# Sheet.net
KiCad netlist of a schematic drawn in Altium Designer
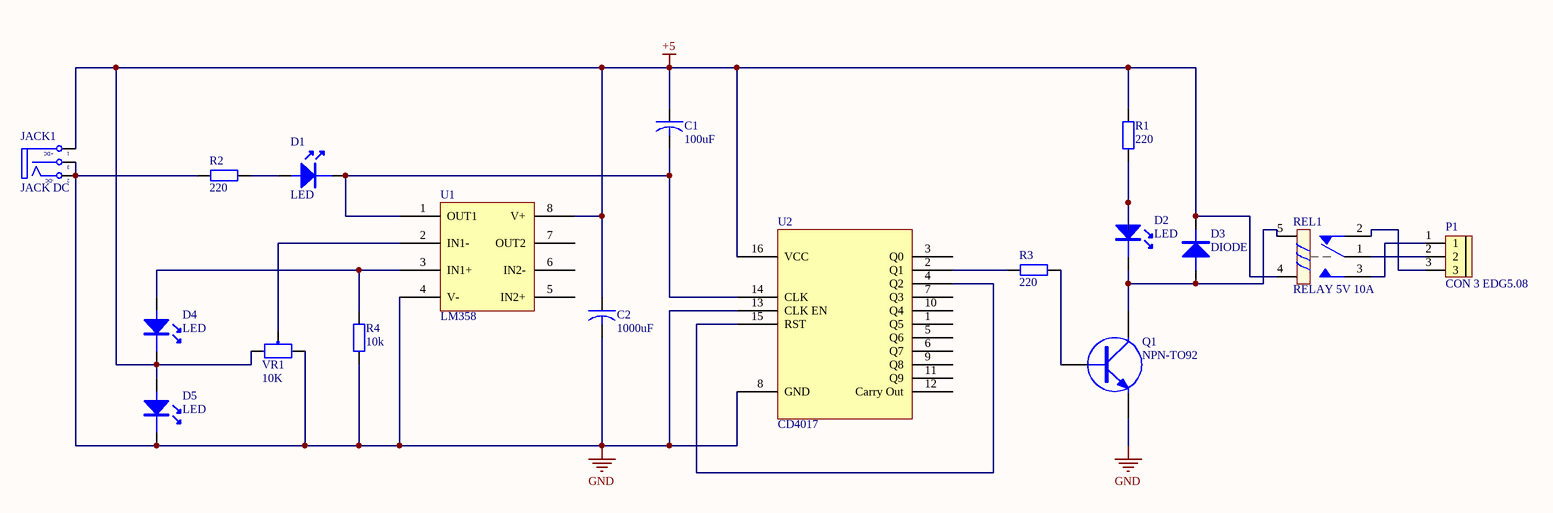
[diagram p0: Sheet.SchDoc]

(export (version "E")
  (design (tool "Eeschema 10.0.6"))
  (components
    (comp (ref "C1") (value "100uF") (footprint "TU HOA 8mm") (libsource (lib "bethu") (part "CAPACITOR")))
    (comp (ref "C2") (value "1000uF") (footprint "TU HOA 8mm") (libsource (lib "bethu") (part "CAPACITOR")))
    (comp (ref "D1") (value "LED") (footprint "LED5MM RED") (libsource (lib "bethu") (part "LED")))
    (comp (ref "D2") (value "LED") (footprint "LED5MM RED") (libsource (lib "bethu") (part "LED")))
    (comp (ref "D3") (value "DIODE") (footprint "DIODE 1A") (libsource (lib "bethu") (part "DIODE")))
    (comp (ref "D4") (value "LED") (footprint "LED5MM RED") (libsource (lib "bethu") (part "LED")))
    (comp (ref "D5") (value "LED") (footprint "LED5MM RED") (libsource (lib "bethu") (part "LED")))
    (comp (ref "JACK1") (value "JACK DC") (footprint "JACK DC") (libsource (lib "bethu") (part "JACK DC")))
    (comp (ref "P1")
      (value "CON 3 EDG5.08")
      (footprint "CON 3P 5.08MM")
      (description "Cắm")
      (libsource (lib "bethu") (part "CON 3 EDG5.08"))
    )
    (comp (ref "Q1") (value "NPN-TO92") (footprint "TO-92") (libsource (lib "bethu") (part "NPN-TO92")))
    (comp (ref "R1") (value "220") (footprint "RESISTOR") (libsource (lib "bethu") (part "RESISTOR")))
    (comp (ref "R2") (value "220") (footprint "RESISTOR") (libsource (lib "bethu") (part "RESISTOR")))
    (comp (ref "R3") (value "220") (footprint "RESISTOR") (libsource (lib "bethu") (part "RESISTOR")))
    (comp (ref "R4") (value "10k") (footprint "RESISTOR") (libsource (lib "bethu") (part "RESISTOR")))
    (comp (ref "REL1")
      (value "RELAY 5V 10A")
      (footprint "RELAY 5V-10A")
      (libsource (lib "bethu") (part "RELAY 5V 10A"))
    )
    (comp (ref "U1") (value "LM358") (footprint "DIP 8") (libsource (lib "bethu") (part "LM358")))
    (comp (ref "U2") (value "CD4017") (footprint "PDIP16") (libsource (lib "bethu") (part "CD4017")))
    (comp (ref "VR1") (value "10K") (footprint "RVAR") (libsource (lib "bethu") (part "VAR RES")))
  )
  (nets
    (net (code "1") (name "+5") (class "Default")
      (node (ref "C1") (pin "1") (pinfunction "1_1") (pintype "passive"))
      (node (ref "C2") (pin "1") (pinfunction "1_1") (pintype "passive"))
      (node (ref "D3") (pin "2") (pinfunction "2_2") (pintype "passive"))
      (node (ref "D4") (pin "2") (pinfunction "2_2") (pintype "passive"))
      (node (ref "D5") (pin "1") (pinfunction "1_1") (pintype "passive"))
      (node (ref "JACK1") (pin "1") (pinfunction "T_1") (pintype "passive"))
      (node (ref "R1") (pin "1") (pinfunction "1_1") (pintype "passive"))
      (node (ref "REL1") (pin "4") (pinfunction "4_4") (pintype "passive"))
      (node (ref "U1") (pin "8") (pinfunction "V+_8") (pintype "passive"))
      (node (ref "U2") (pin "16") (pinfunction "VCC_16") (pintype "passive"))
      (node (ref "VR1") (pin "1") (pinfunction "1_1") (pintype "passive"))
    )
    (net (code "2") (name "GND") (class "Default")
      (node (ref "C2") (pin "2") (pinfunction "2_2") (pintype "passive"))
      (node (ref "D5") (pin "2") (pinfunction "2_2") (pintype "passive"))
      (node (ref "JACK1") (pin "2") (pinfunction "TN_2") (pintype "passive"))
      (node (ref "JACK1") (pin "3") (pinfunction "S_3") (pintype "power_in"))
      (node (ref "Q1") (pin "1") (pinfunction "E_1") (pintype "passive"))
      (node (ref "R2") (pin "1") (pinfunction "1_1") (pintype "passive"))
      (node (ref "R4") (pin "1") (pinfunction "1_1") (pintype "passive"))
      (node (ref "U1") (pin "4") (pinfunction "V-_4") (pintype "passive"))
      (node (ref "U2") (pin "13") (pinfunction "CLK_EN_13") (pintype "passive"))
      (node (ref "U2") (pin "8") (pinfunction "GND_8") (pintype "passive"))
      (node (ref "VR1") (pin "3") (pinfunction "3_3") (pintype "passive"))
    )
    (net (code "3") (name "Net-(D1-Pad1)") (class "Default")
      (node (ref "D1") (pin "1") (pinfunction "1_1") (pintype "passive"))
      (node (ref "R2") (pin "2") (pinfunction "2_2") (pintype "passive"))
    )
    (net (code "4") (name "Net-(D2-Pad1)") (class "Default")
      (node (ref "D2") (pin "1") (pinfunction "1_1") (pintype "passive"))
      (node (ref "R1") (pin "2") (pinfunction "2_2") (pintype "passive"))
    )
    (net (code "5") (name "Net-(P1-Pad1)") (class "Default")
      (node (ref "P1") (pin "1") (pinfunction "1_1") (pintype "passive"))
      (node (ref "REL1") (pin "3") (pinfunction "3_3") (pintype "passive"))
    )
    (net (code "6") (name "Net-(P1-Pad2)") (class "Default")
      (node (ref "P1") (pin "2") (pinfunction "2_2") (pintype "passive"))
      (node (ref "REL1") (pin "1") (pinfunction "1_1") (pintype "passive"))
    )
    (net (code "7") (name "Net-(P1-Pad3)") (class "Default")
      (node (ref "P1") (pin "3") (pinfunction "3_3") (pintype "passive"))
      (node (ref "REL1") (pin "2") (pinfunction "2_2") (pintype "passive"))
    )
    (net (code "8") (name "Net-(Q1-B)") (class "Default")
      (node (ref "Q1") (pin "3") (pinfunction "B_3") (pintype "passive"))
      (node (ref "R3") (pin "2") (pinfunction "2_2") (pintype "passive"))
    )
    (net (code "9") (name "Net-(Q1-C)") (class "Default")
      (node (ref "D2") (pin "2") (pinfunction "2_2") (pintype "passive"))
      (node (ref "D3") (pin "1") (pinfunction "1_1") (pintype "passive"))
      (node (ref "Q1") (pin "2") (pinfunction "C_2") (pintype "passive"))
      (node (ref "REL1") (pin "5") (pinfunction "5_5") (pintype "passive"))
    )
    (net (code "10") (name "Net-(U1-IN1+)") (class "Default")
      (node (ref "D4") (pin "1") (pinfunction "1_1") (pintype "passive"))
      (node (ref "R4") (pin "2") (pinfunction "2_2") (pintype "passive"))
      (node (ref "U1") (pin "3") (pinfunction "IN1+_3") (pintype "passive"))
    )
    (net (code "11") (name "Net-(U1-IN1-)") (class "Default")
      (node (ref "U1") (pin "2") (pinfunction "IN1-_2") (pintype "passive"))
      (node (ref "VR1") (pin "2") (pinfunction "2_2") (pintype "passive"))
    )
    (net (code "12") (name "Net-(U1-OUT1)") (class "Default")
      (node (ref "C1") (pin "2") (pinfunction "2_2") (pintype "passive"))
      (node (ref "D1") (pin "2") (pinfunction "2_2") (pintype "passive"))
      (node (ref "U1") (pin "1") (pinfunction "OUT1_1") (pintype "passive"))
      (node (ref "U2") (pin "14") (pinfunction "CLK_14") (pintype "passive"))
    )
    (net (code "13") (name "Net-(U2-Q1)") (class "Default")
      (node (ref "R3") (pin "1") (pinfunction "1_1") (pintype "passive"))
      (node (ref "U2") (pin "2") (pinfunction "Q1_2") (pintype "passive"))
    )
    (net (code "14") (name "Net-(U2-Q2)") (class "Default")
      (node (ref "U2") (pin "15") (pinfunction "RST_15") (pintype "passive"))
      (node (ref "U2") (pin "4") (pinfunction "Q2_4") (pintype "passive"))
    )
    (net (code "15") (name "unconnected-(U1-IN2+-Pad5)") (class "Default")
      (node (ref "U1") (pin "5") (pinfunction "IN2+_5") (pintype "passive"))
    )
    (net (code "16") (name "unconnected-(U1-IN2--Pad6)") (class "Default")
      (node (ref "U1") (pin "6") (pinfunction "IN2-_6") (pintype "passive"))
    )
    (net (code "17") (name "unconnected-(U1-OUT2-Pad7)") (class "Default")
      (node (ref "U1") (pin "7") (pinfunction "OUT2_7") (pintype "passive"))
    )
    (net (code "18") (name "unconnected-(U2-Carry_Out-Pad12)") (class "Default")
      (node (ref "U2") (pin "12") (pinfunction "Carry_Out_12") (pintype "passive"))
    )
    (net (code "19") (name "unconnected-(U2-Q0-Pad3)") (class "Default")
      (node (ref "U2") (pin "3") (pinfunction "Q0_3") (pintype "passive"))
    )
    (net (code "20") (name "unconnected-(U2-Q3-Pad7)") (class "Default")
      (node (ref "U2") (pin "7") (pinfunction "Q3_7") (pintype "passive"))
    )
    (net (code "21") (name "unconnected-(U2-Q4-Pad10)") (class "Default")
      (node (ref "U2") (pin "10") (pinfunction "Q4_10") (pintype "passive"))
    )
    (net (code "22") (name "unconnected-(U2-Q5-Pad1)") (class "Default")
      (node (ref "U2") (pin "1") (pinfunction "Q5_1") (pintype "passive"))
    )
    (net (code "23") (name "unconnected-(U2-Q6-Pad5)") (class "Default")
      (node (ref "U2") (pin "5") (pinfunction "Q6_5") (pintype "passive"))
    )
    (net (code "24") (name "unconnected-(U2-Q7-Pad6)") (class "Default")
      (node (ref "U2") (pin "6") (pinfunction "Q7_6") (pintype "passive"))
    )
    (net (code "25") (name "unconnected-(U2-Q8-Pad9)") (class "Default")
      (node (ref "U2") (pin "9") (pinfunction "Q8_9") (pintype "passive"))
    )
    (net (code "26") (name "unconnected-(U2-Q9-Pad11)") (class "Default")
      (node (ref "U2") (pin "11") (pinfunction "Q9_11") (pintype "passive"))
    )
  )
)
